# InterfazSensores.net
KiCad netlist of a schematic drawn in EAGLE
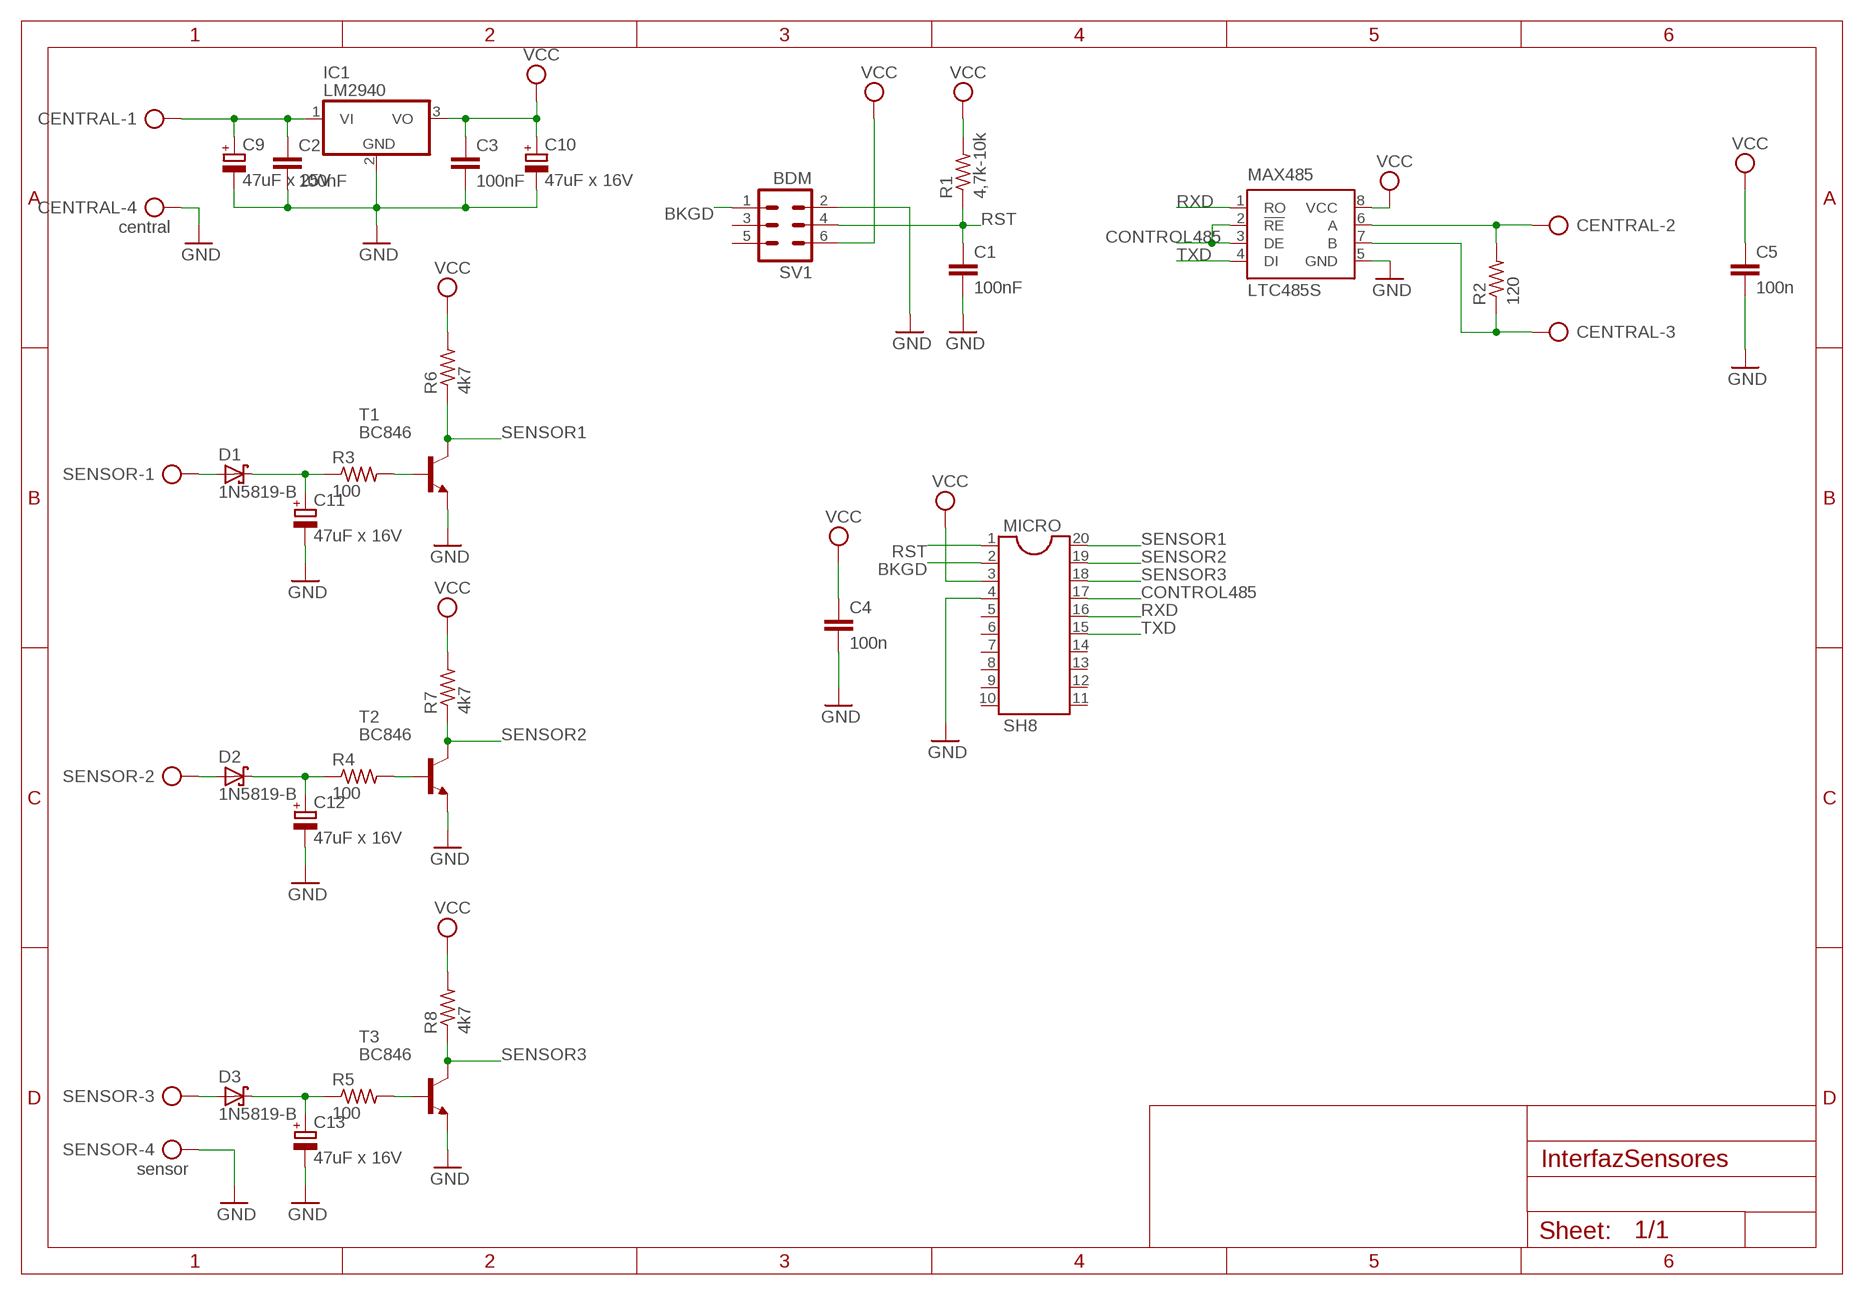
[diagram p0: schematic, sheet 1]

(export (version "E")
  (design (tool "Eeschema 10.0.6"))
  (components
    (comp (ref "C1")
      (value "100nF")
      (footprint "eagle-import:C0805")
      (libsource (lib "eagle-import") (part "C-EUC0805"))
    )
    (comp (ref "C2")
      (value "100nF")
      (footprint "eagle-import:C0805")
      (libsource (lib "eagle-import") (part "C-EUC0805"))
    )
    (comp (ref "C3")
      (value "100nF")
      (footprint "eagle-import:C0805")
      (libsource (lib "eagle-import") (part "C-EUC0805"))
    )
    (comp (ref "C4")
      (value "100n")
      (footprint "eagle-import:C0805")
      (libsource (lib "eagle-import") (part "C-EUC0805"))
    )
    (comp (ref "C5")
      (value "100n")
      (footprint "eagle-import:C0805")
      (libsource (lib "eagle-import") (part "C-EUC0805"))
    )
    (comp (ref "C9")
      (value "47uF x 25V")
      (footprint "eagle-import:E2,5-6E")
      (libsource (lib "eagle-import") (part "CPOL-EUE2,5-6E"))
    )
    (comp (ref "C10")
      (value "47uF x 16V")
      (footprint "eagle-import:E2,5-6E")
      (libsource (lib "eagle-import") (part "CPOL-EUE2,5-6E"))
    )
    (comp (ref "C11")
      (value "47uF x 16V")
      (footprint "eagle-import:E2,5-6E")
      (libsource (lib "eagle-import") (part "CPOL-EUE2,5-6E"))
    )
    (comp (ref "C12")
      (value "47uF x 16V")
      (footprint "eagle-import:E2,5-6E")
      (libsource (lib "eagle-import") (part "CPOL-EUE2,5-6E"))
    )
    (comp (ref "C13")
      (value "47uF x 16V")
      (footprint "eagle-import:E2,5-6E")
      (libsource (lib "eagle-import") (part "CPOL-EUE2,5-6E"))
    )
    (comp (ref "CENTRAL")
      (value "central")
      (footprint "eagle-import:AK300_4")
      (libsource (lib "eagle-import") (part "AK300/4"))
    )
    (comp (ref "D1")
      (value "1N5819-B")
      (footprint "eagle-import:DO41-7.6")
      (libsource (lib "eagle-import") (part "1N5819-B"))
    )
    (comp (ref "D2")
      (value "1N5819-B")
      (footprint "eagle-import:DO41-7.6")
      (libsource (lib "eagle-import") (part "1N5819-B"))
    )
    (comp (ref "D3")
      (value "1N5819-B")
      (footprint "eagle-import:DO41-7.6")
      (libsource (lib "eagle-import") (part "1N5819-B"))
    )
    (comp (ref "IC1")
      (value "LM2940")
      (footprint "eagle-import:TO220V")
      (libsource (lib "eagle-import") (part "78TV05"))
    )
    (comp (ref "MAX485")
      (value "LTC485S")
      (footprint "eagle-import:SOIC8")
      (libsource (lib "eagle-import") (part "LTC485S"))
    )
    (comp (ref "MICRO")
      (value "SH8")
      (footprint "eagle-import:DIL20")
      (libsource (lib "eagle-import") (part "DIL20"))
    )
    (comp (ref "R1")
      (value "4,7k-10k")
      (footprint "eagle-import:R0805")
      (libsource (lib "eagle-import") (part "R-US_R0805"))
    )
    (comp (ref "R2")
      (value "120")
      (footprint "eagle-import:R0805")
      (libsource (lib "eagle-import") (part "R-US_R0805"))
    )
    (comp (ref "R3")
      (value "100")
      (footprint "eagle-import:R0805")
      (libsource (lib "eagle-import") (part "R-US_R0805"))
    )
    (comp (ref "R4")
      (value "100")
      (footprint "eagle-import:R0805")
      (libsource (lib "eagle-import") (part "R-US_R0805"))
    )
    (comp (ref "R5")
      (value "100")
      (footprint "eagle-import:R0805")
      (libsource (lib "eagle-import") (part "R-US_R0805"))
    )
    (comp (ref "R6")
      (value "4k7")
      (footprint "eagle-import:R0805")
      (libsource (lib "eagle-import") (part "R-US_R0805"))
    )
    (comp (ref "R7")
      (value "4k7")
      (footprint "eagle-import:R0805")
      (libsource (lib "eagle-import") (part "R-US_R0805"))
    )
    (comp (ref "R8")
      (value "4k7")
      (footprint "eagle-import:R0805")
      (libsource (lib "eagle-import") (part "R-US_R0805"))
    )
    (comp (ref "SENSOR")
      (value "sensor")
      (footprint "eagle-import:AK300_4")
      (libsource (lib "eagle-import") (part "AK300/4"))
    )
    (comp (ref "SV1")
      (value "BDM")
      (footprint "eagle-import:MA03-2")
      (libsource (lib "eagle-import") (part "MA03-2"))
    )
    (comp (ref "T1")
      (value "BC846")
      (footprint "eagle-import:SOT23")
      (libsource (lib "eagle-import") (part "BC846"))
    )
    (comp (ref "T2")
      (value "BC846")
      (footprint "eagle-import:SOT23")
      (libsource (lib "eagle-import") (part "BC846"))
    )
    (comp (ref "T3")
      (value "BC846")
      (footprint "eagle-import:SOT23")
      (libsource (lib "eagle-import") (part "BC846"))
    )
  )
  (nets
    (net (code "1") (name "/BKGD") (class "Default")
      (node (ref "MICRO") (pin "2") (pinfunction "2_2") (pintype "passive"))
      (node (ref "SV1") (pin "1") (pinfunction "1_1") (pintype "passive"))
    )
    (net (code "2") (name "/CONTROL485") (class "Default")
      (node (ref "MAX485") (pin "2") (pinfunction "~{RE}_2") (pintype "input"))
      (node (ref "MAX485") (pin "3") (pinfunction "DE_3") (pintype "input"))
      (node (ref "MICRO") (pin "17") (pinfunction "17_17") (pintype "passive"))
    )
    (net (code "3") (name "/RST") (class "Default")
      (node (ref "C1") (pin "1") (pinfunction "1_1") (pintype "passive"))
      (node (ref "MICRO") (pin "1") (pinfunction "1_1") (pintype "passive"))
      (node (ref "R1") (pin "1") (pinfunction "1_1") (pintype "passive"))
      (node (ref "SV1") (pin "4") (pinfunction "4_4") (pintype "passive"))
    )
    (net (code "4") (name "/RXD") (class "Default")
      (node (ref "MAX485") (pin "1") (pinfunction "RO_1") (pintype "output"))
      (node (ref "MICRO") (pin "16") (pinfunction "16_16") (pintype "passive"))
    )
    (net (code "5") (name "/SENSOR1") (class "Default")
      (node (ref "MICRO") (pin "20") (pinfunction "20_20") (pintype "passive"))
      (node (ref "R6") (pin "1") (pinfunction "1_1") (pintype "passive"))
      (node (ref "T1") (pin "3") (pinfunction "C_3") (pintype "passive"))
    )
    (net (code "6") (name "/SENSOR2") (class "Default")
      (node (ref "MICRO") (pin "19") (pinfunction "19_19") (pintype "passive"))
      (node (ref "R7") (pin "1") (pinfunction "1_1") (pintype "passive"))
      (node (ref "T2") (pin "3") (pinfunction "C_3") (pintype "passive"))
    )
    (net (code "7") (name "/SENSOR3") (class "Default")
      (node (ref "MICRO") (pin "18") (pinfunction "18_18") (pintype "passive"))
      (node (ref "R8") (pin "1") (pinfunction "1_1") (pintype "passive"))
      (node (ref "T3") (pin "3") (pinfunction "C_3") (pintype "passive"))
    )
    (net (code "8") (name "/TXD") (class "Default")
      (node (ref "MAX485") (pin "4") (pinfunction "DI_4") (pintype "input"))
      (node (ref "MICRO") (pin "15") (pinfunction "15_15") (pintype "passive"))
    )
    (net (code "9") (name "GND") (class "Default")
      (node (ref "C1") (pin "2") (pinfunction "2_2") (pintype "passive"))
      (node (ref "C10") (pin "-") (pinfunction "-_-") (pintype "passive"))
      (node (ref "C11") (pin "-") (pinfunction "-_-") (pintype "passive"))
      (node (ref "C12") (pin "-") (pinfunction "-_-") (pintype "passive"))
      (node (ref "C13") (pin "-") (pinfunction "-_-") (pintype "passive"))
      (node (ref "C2") (pin "2") (pinfunction "2_2") (pintype "passive"))
      (node (ref "C3") (pin "2") (pinfunction "2_2") (pintype "passive"))
      (node (ref "C4") (pin "2") (pinfunction "2_2") (pintype "passive"))
      (node (ref "C5") (pin "2") (pinfunction "2_2") (pintype "passive"))
      (node (ref "C9") (pin "-") (pinfunction "-_-") (pintype "passive"))
      (node (ref "CENTRAL") (pin "4") (pinfunction "KL_4") (pintype "passive"))
      (node (ref "IC1") (pin "2") (pinfunction "GND_2") (pintype "passive"))
      (node (ref "MAX485") (pin "5") (pinfunction "GND_5") (pintype "input"))
      (node (ref "MICRO") (pin "4") (pinfunction "4_4") (pintype "passive"))
      (node (ref "SENSOR") (pin "4") (pinfunction "KL_4") (pintype "passive"))
      (node (ref "SV1") (pin "2") (pinfunction "2_2") (pintype "passive"))
      (node (ref "T1") (pin "2") (pinfunction "E_2") (pintype "passive"))
      (node (ref "T2") (pin "2") (pinfunction "E_2") (pintype "passive"))
      (node (ref "T3") (pin "2") (pinfunction "E_2") (pintype "passive"))
    )
    (net (code "10") (name "Net-(C11-Pad+)") (class "Default")
      (node (ref "C11") (pin "+") (pinfunction "+_+") (pintype "passive"))
      (node (ref "D1") (pin "C") (pinfunction "C_C") (pintype "passive"))
      (node (ref "R3") (pin "1") (pinfunction "1_1") (pintype "passive"))
    )
    (net (code "11") (name "Net-(C12-Pad+)") (class "Default")
      (node (ref "C12") (pin "+") (pinfunction "+_+") (pintype "passive"))
      (node (ref "D2") (pin "C") (pinfunction "C_C") (pintype "passive"))
      (node (ref "R4") (pin "1") (pinfunction "1_1") (pintype "passive"))
    )
    (net (code "12") (name "Net-(C13-Pad+)") (class "Default")
      (node (ref "C13") (pin "+") (pinfunction "+_+") (pintype "passive"))
      (node (ref "D3") (pin "C") (pinfunction "C_C") (pintype "passive"))
      (node (ref "R5") (pin "1") (pinfunction "1_1") (pintype "passive"))
    )
    (net (code "13") (name "Net-(CENTRALA-KL)") (class "Default")
      (node (ref "C2") (pin "1") (pinfunction "1_1") (pintype "passive"))
      (node (ref "C9") (pin "+") (pinfunction "+_+") (pintype "passive"))
      (node (ref "CENTRAL") (pin "1") (pinfunction "KL_1") (pintype "passive"))
      (node (ref "IC1") (pin "1") (pinfunction "VI_1") (pintype "input"))
    )
    (net (code "14") (name "Net-(CENTRALB-KL)") (class "Default")
      (node (ref "CENTRAL") (pin "2") (pinfunction "KL_2") (pintype "passive"))
      (node (ref "MAX485") (pin "6") (pinfunction "A_6") (pintype "bidirectional"))
      (node (ref "R2") (pin "2") (pinfunction "2_2") (pintype "passive"))
    )
    (net (code "15") (name "Net-(CENTRALC-KL)") (class "Default")
      (node (ref "CENTRAL") (pin "3") (pinfunction "KL_3") (pintype "passive"))
      (node (ref "MAX485") (pin "7") (pinfunction "B_7") (pintype "bidirectional"))
      (node (ref "R2") (pin "1") (pinfunction "1_1") (pintype "passive"))
    )
    (net (code "16") (name "Net-(SENSORA-KL)") (class "Default")
      (node (ref "D1") (pin "A") (pinfunction "A_A") (pintype "passive"))
      (node (ref "SENSOR") (pin "1") (pinfunction "KL_1") (pintype "passive"))
    )
    (net (code "17") (name "Net-(SENSORB-KL)") (class "Default")
      (node (ref "D2") (pin "A") (pinfunction "A_A") (pintype "passive"))
      (node (ref "SENSOR") (pin "2") (pinfunction "KL_2") (pintype "passive"))
    )
    (net (code "18") (name "Net-(SENSORC-KL)") (class "Default")
      (node (ref "D3") (pin "A") (pinfunction "A_A") (pintype "passive"))
      (node (ref "SENSOR") (pin "3") (pinfunction "KL_3") (pintype "passive"))
    )
    (net (code "19") (name "Net-(T1-B)") (class "Default")
      (node (ref "R3") (pin "2") (pinfunction "2_2") (pintype "passive"))
      (node (ref "T1") (pin "1") (pinfunction "B_1") (pintype "passive"))
    )
    (net (code "20") (name "Net-(T2-B)") (class "Default")
      (node (ref "R4") (pin "2") (pinfunction "2_2") (pintype "passive"))
      (node (ref "T2") (pin "1") (pinfunction "B_1") (pintype "passive"))
    )
    (net (code "21") (name "Net-(T3-B)") (class "Default")
      (node (ref "R5") (pin "2") (pinfunction "2_2") (pintype "passive"))
      (node (ref "T3") (pin "1") (pinfunction "B_1") (pintype "passive"))
    )
    (net (code "22") (name "VCC") (class "Default")
      (node (ref "C10") (pin "+") (pinfunction "+_+") (pintype "passive"))
      (node (ref "C3") (pin "1") (pinfunction "1_1") (pintype "passive"))
      (node (ref "C4") (pin "1") (pinfunction "1_1") (pintype "passive"))
      (node (ref "C5") (pin "1") (pinfunction "1_1") (pintype "passive"))
      (node (ref "IC1") (pin "3") (pinfunction "VO_3") (pintype "passive"))
      (node (ref "MAX485") (pin "8") (pinfunction "VCC_8") (pintype "input"))
      (node (ref "MICRO") (pin "3") (pinfunction "3_3") (pintype "passive"))
      (node (ref "R1") (pin "2") (pinfunction "2_2") (pintype "passive"))
      (node (ref "R6") (pin "2") (pinfunction "2_2") (pintype "passive"))
      (node (ref "R7") (pin "2") (pinfunction "2_2") (pintype "passive"))
      (node (ref "R8") (pin "2") (pinfunction "2_2") (pintype "passive"))
      (node (ref "SV1") (pin "6") (pinfunction "6_6") (pintype "passive"))
    )
    (net (code "23") (name "unconnected-(MICRO-Pad5)") (class "Default")
      (node (ref "MICRO") (pin "5") (pinfunction "5_5") (pintype "passive"))
    )
    (net (code "24") (name "unconnected-(MICRO-Pad6)") (class "Default")
      (node (ref "MICRO") (pin "6") (pinfunction "6_6") (pintype "passive"))
    )
    (net (code "25") (name "unconnected-(MICRO-Pad7)") (class "Default")
      (node (ref "MICRO") (pin "7") (pinfunction "7_7") (pintype "passive"))
    )
    (net (code "26") (name "unconnected-(MICRO-Pad8)") (class "Default")
      (node (ref "MICRO") (pin "8") (pinfunction "8_8") (pintype "passive"))
    )
    (net (code "27") (name "unconnected-(MICRO-Pad9)") (class "Default")
      (node (ref "MICRO") (pin "9") (pinfunction "9_9") (pintype "passive"))
    )
    (net (code "28") (name "unconnected-(MICRO-Pad10)") (class "Default")
      (node (ref "MICRO") (pin "10") (pinfunction "10_10") (pintype "passive"))
    )
    (net (code "29") (name "unconnected-(MICRO-Pad11)") (class "Default")
      (node (ref "MICRO") (pin "11") (pinfunction "11_11") (pintype "passive"))
    )
    (net (code "30") (name "unconnected-(MICRO-Pad12)") (class "Default")
      (node (ref "MICRO") (pin "12") (pinfunction "12_12") (pintype "passive"))
    )
    (net (code "31") (name "unconnected-(MICRO-Pad13)") (class "Default")
      (node (ref "MICRO") (pin "13") (pinfunction "13_13") (pintype "passive"))
    )
    (net (code "32") (name "unconnected-(MICRO-Pad14)") (class "Default")
      (node (ref "MICRO") (pin "14") (pinfunction "14_14") (pintype "passive"))
    )
    (net (code "33") (name "unconnected-(SV1-Pad3)") (class "Default")
      (node (ref "SV1") (pin "3") (pinfunction "3_3") (pintype "passive"))
    )
    (net (code "34") (name "unconnected-(SV1-Pad5)") (class "Default")
      (node (ref "SV1") (pin "5") (pinfunction "5_5") (pintype "passive"))
    )
  )
)
